# Dual_Power_Supply.net
KiCad netlist of a schematic drawn in EAGLE
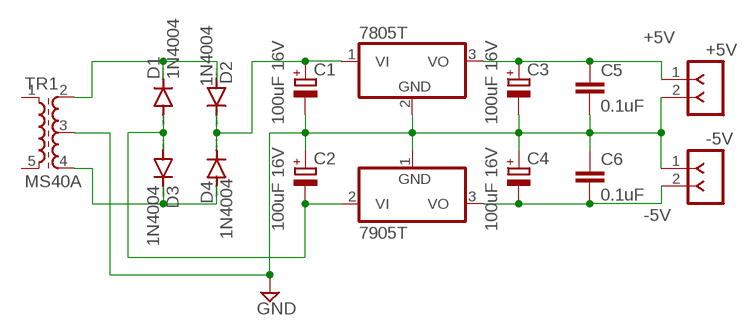
[diagram p0: schematic, sheet 1]

(export (version "E")
  (design (tool "Eeschema 10.0.6"))
  (components
    (comp (ref "+5V")
      (value "F-1X02-SIP-100-40Y")
      (footprint "eagle-import:SIP-100-02-40Y")
      (libsource (lib "eagle-import") (part "F-1X02-SIP-100-40Y"))
    )
    (comp (ref "-5V")
      (value "F-1X02-SIP-100-40Y")
      (footprint "eagle-import:SIP-100-02-40Y")
      (libsource (lib "eagle-import") (part "F-1X02-SIP-100-40Y"))
    )
    (comp (ref "7805T")
      (value "7805T")
      (footprint "eagle-import:TO220H")
      (libsource (lib "eagle-import") (part "78T05"))
    )
    (comp (ref "7905T")
      (value "7905T")
      (footprint "eagle-import:TO220H")
      (libsource (lib "eagle-import") (part "79T05"))
    )
    (comp (ref "C1")
      (value "100uF 16V")
      (footprint "eagle-import:SANYO-OSCON_C6")
      (libsource (lib "eagle-import") (part "CPOL-EUSANYO_C6"))
    )
    (comp (ref "C2")
      (value "100uF 16V")
      (footprint "eagle-import:SANYO-OSCON_C6")
      (libsource (lib "eagle-import") (part "CPOL-EUSANYO_C6"))
    )
    (comp (ref "C3")
      (value "100uF 16V")
      (footprint "eagle-import:SANYO-OSCON_C6")
      (libsource (lib "eagle-import") (part "CPOL-EUSANYO_C6"))
    )
    (comp (ref "C4")
      (value "100uF 16V")
      (footprint "eagle-import:SANYO-OSCON_C6")
      (libsource (lib "eagle-import") (part "CPOL-EUSANYO_C6"))
    )
    (comp (ref "C5")
      (value "0.1uF")
      (footprint "eagle-import:C025-024X044")
      (libsource (lib "eagle-import") (part "C-EU025-024X044"))
    )
    (comp (ref "C6")
      (value "0.1uF")
      (footprint "eagle-import:C025-024X044")
      (libsource (lib "eagle-import") (part "C-EU025-024X044"))
    )
    (comp (ref "D1")
      (value "1N4004")
      (footprint "eagle-import:DO41-10")
      (libsource (lib "eagle-import") (part "1N4004"))
    )
    (comp (ref "D2")
      (value "1N4004")
      (footprint "eagle-import:DO41-10")
      (libsource (lib "eagle-import") (part "1N4004"))
    )
    (comp (ref "D3")
      (value "1N4004")
      (footprint "eagle-import:DO41-10")
      (libsource (lib "eagle-import") (part "1N4004"))
    )
    (comp (ref "D4")
      (value "1N4004")
      (footprint "eagle-import:DO41-10")
      (libsource (lib "eagle-import") (part "1N4004"))
    )
    (comp (ref "TR1")
      (value "MS40A")
      (footprint "eagle-import:MS40")
      (libsource (lib "eagle-import") (part "MS40A"))
    )
  )
  (nets
    (net (code "1") (name "/+5V") (class "Default")
      (node (ref "+5V") (pin "1") (pinfunction "1_1") (pintype "passive"))
      (node (ref "7805T") (pin "3") (pinfunction "VO_3") (pintype "passive"))
      (node (ref "C3") (pin "+") (pinfunction "+_+") (pintype "passive"))
      (node (ref "C5") (pin "1") (pinfunction "1_1") (pintype "passive"))
    )
    (net (code "2") (name "/-5V") (class "Default")
      (node (ref "-5V") (pin "2") (pinfunction "2_2") (pintype "passive"))
      (node (ref "7905T") (pin "3") (pinfunction "VO_3") (pintype "passive"))
      (node (ref "C4") (pin "-") (pinfunction "-_-") (pintype "passive"))
      (node (ref "C6") (pin "2") (pinfunction "2_2") (pintype "passive"))
    )
    (net (code "3") (name "GND") (class "Default")
      (node (ref "+5V") (pin "2") (pinfunction "2_2") (pintype "passive"))
      (node (ref "-5V") (pin "1") (pinfunction "1_1") (pintype "passive"))
      (node (ref "7805T") (pin "2") (pinfunction "GND_2") (pintype "passive"))
      (node (ref "7905T") (pin "1") (pinfunction "GND_1") (pintype "passive"))
      (node (ref "C1") (pin "-") (pinfunction "-_-") (pintype "passive"))
      (node (ref "C2") (pin "+") (pinfunction "+_+") (pintype "passive"))
      (node (ref "C3") (pin "-") (pinfunction "-_-") (pintype "passive"))
      (node (ref "C4") (pin "+") (pinfunction "+_+") (pintype "passive"))
      (node (ref "C5") (pin "2") (pinfunction "2_2") (pintype "passive"))
      (node (ref "C6") (pin "1") (pinfunction "1_1") (pintype "passive"))
      (node (ref "TR1") (pin "3") (pinfunction "3_3") (pintype "passive"))
    )
    (net (code "4") (name "Net-(7805T-VI)") (class "Default")
      (node (ref "7805T") (pin "1") (pinfunction "VI_1") (pintype "input"))
      (node (ref "C1") (pin "+") (pinfunction "+_+") (pintype "passive"))
      (node (ref "D2") (pin "C") (pinfunction "C_C") (pintype "passive"))
      (node (ref "D4") (pin "C") (pinfunction "C_C") (pintype "passive"))
    )
    (net (code "5") (name "Net-(7905T-VI)") (class "Default")
      (node (ref "7905T") (pin "2") (pinfunction "VI_2") (pintype "input"))
      (node (ref "C2") (pin "-") (pinfunction "-_-") (pintype "passive"))
      (node (ref "D1") (pin "A") (pinfunction "A_A") (pintype "passive"))
      (node (ref "D3") (pin "A") (pinfunction "A_A") (pintype "passive"))
    )
    (net (code "6") (name "Net-(D1-PadC)") (class "Default")
      (node (ref "D1") (pin "C") (pinfunction "C_C") (pintype "passive"))
      (node (ref "D2") (pin "A") (pinfunction "A_A") (pintype "passive"))
      (node (ref "TR1") (pin "2") (pinfunction "2_2") (pintype "passive"))
    )
    (net (code "7") (name "Net-(D3-PadC)") (class "Default")
      (node (ref "D3") (pin "C") (pinfunction "C_C") (pintype "passive"))
      (node (ref "D4") (pin "A") (pinfunction "A_A") (pintype "passive"))
      (node (ref "TR1") (pin "4") (pinfunction "4_4") (pintype "passive"))
    )
    (net (code "8") (name "unconnected-(TR1-Pad1)") (class "Default")
      (node (ref "TR1") (pin "1") (pinfunction "1_1") (pintype "passive"))
    )
    (net (code "9") (name "unconnected-(TR1-Pad5)") (class "Default")
      (node (ref "TR1") (pin "5") (pinfunction "5_5") (pintype "passive"))
    )
  )
)
